# mega128board.net
KiCad netlist of a schematic drawn in EAGLE
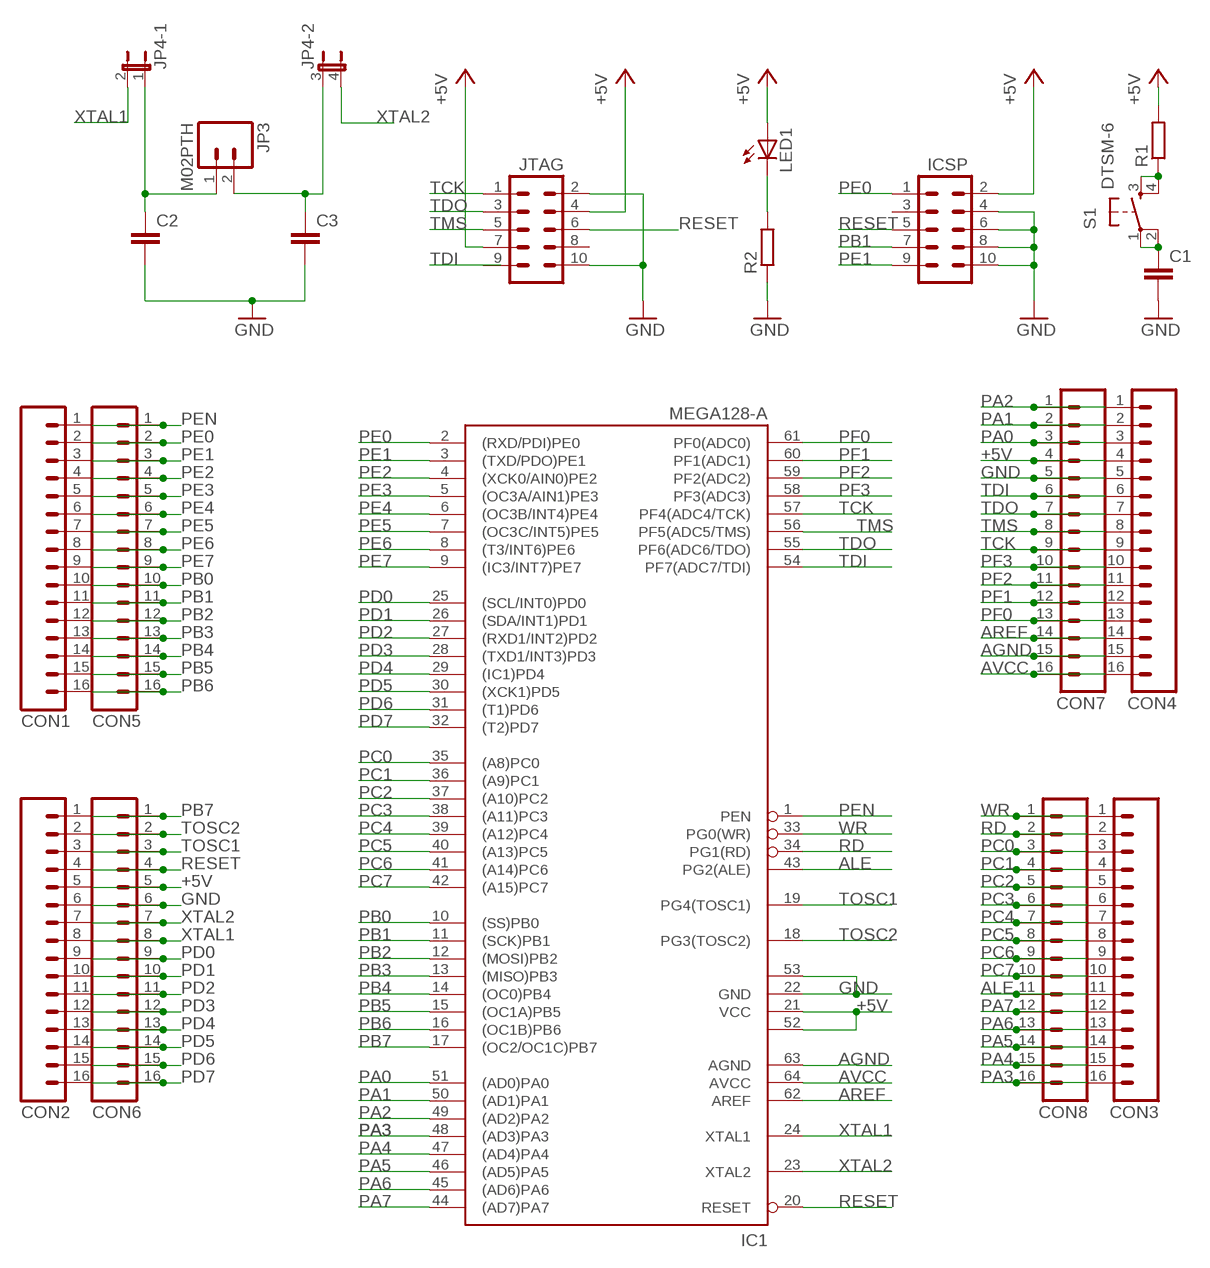
[diagram p0: schematic, sheet 1]

(export (version "E")
  (design (tool "Eeschema 10.0.6"))
  (components
    (comp (ref "C1")
      (value "C-EUC0805")
      (footprint "eagle-import:C0805")
      (libsource (lib "eagle-import") (part "C-EUC0805"))
    )
    (comp (ref "C2")
      (value "C-EUC0805")
      (footprint "eagle-import:C0805")
      (libsource (lib "eagle-import") (part "C-EUC0805"))
    )
    (comp (ref "C3")
      (value "C-EUC0805")
      (footprint "eagle-import:C0805")
      (libsource (lib "eagle-import") (part "C-EUC0805"))
    )
    (comp (ref "CON1")
      (value "M161X16_NO_SILK")
      (footprint "eagle-import:1X16_NO_SILK")
      (libsource (lib "eagle-import") (part "M161X16_NO_SILK"))
    )
    (comp (ref "CON2")
      (value "M161X16_NO_SILK")
      (footprint "eagle-import:1X16_NO_SILK")
      (libsource (lib "eagle-import") (part "M161X16_NO_SILK"))
    )
    (comp (ref "CON3")
      (value "M161X16_NO_SILK")
      (footprint "eagle-import:1X16_NO_SILK")
      (libsource (lib "eagle-import") (part "M161X16_NO_SILK"))
    )
    (comp (ref "CON4")
      (value "M161X16_NO_SILK")
      (footprint "eagle-import:1X16_NO_SILK")
      (libsource (lib "eagle-import") (part "M161X16_NO_SILK"))
    )
    (comp (ref "CON5")
      (value "M161X16_NO_SILK")
      (footprint "eagle-import:1X16_NO_SILK")
      (libsource (lib "eagle-import") (part "M161X16_NO_SILK"))
    )
    (comp (ref "CON6")
      (value "M161X16_NO_SILK")
      (footprint "eagle-import:1X16_NO_SILK")
      (libsource (lib "eagle-import") (part "M161X16_NO_SILK"))
    )
    (comp (ref "CON7")
      (value "M161X16_NO_SILK")
      (footprint "eagle-import:1X16_NO_SILK")
      (libsource (lib "eagle-import") (part "M161X16_NO_SILK"))
    )
    (comp (ref "CON8")
      (value "M161X16_NO_SILK")
      (footprint "eagle-import:1X16_NO_SILK")
      (libsource (lib "eagle-import") (part "M161X16_NO_SILK"))
    )
    (comp (ref "IC1")
      (value "MEGA128-A")
      (footprint "eagle-import:TQFP64")
      (libsource (lib "eagle-import") (part "MEGA128-A"))
    )
    (comp (ref "ICSP")
      (value "M05X2SHD")
      (footprint "eagle-import:2X5-SHROUDED")
      (libsource (lib "eagle-import") (part "M05X2SHD"))
    )
    (comp (ref "JP3")
      (value "M02PTH")
      (footprint "eagle-import:1X02")
      (libsource (lib "eagle-import") (part "M02PTH"))
    )
    (comp (ref "JP4")
      (value "JP2QE")
      (footprint "eagle-import:JP2Q")
      (libsource (lib "eagle-import") (part "JP2QE"))
    )
    (comp (ref "JTAG")
      (value "M05X2SHD")
      (footprint "eagle-import:2X5-SHROUDED")
      (libsource (lib "eagle-import") (part "M05X2SHD"))
    )
    (comp (ref "LED1")
      (value "LED1206")
      (footprint "eagle-import:LED-1206")
      (libsource (lib "eagle-import") (part "LED1206"))
    )
    (comp (ref "R1")
      (value "R-EU_M0805")
      (footprint "eagle-import:M0805")
      (libsource (lib "eagle-import") (part "R-EU_M0805"))
    )
    (comp (ref "R2")
      (value "R-EU_M0805")
      (footprint "eagle-import:M0805")
      (libsource (lib "eagle-import") (part "R-EU_M0805"))
    )
    (comp (ref "S1")
      (value "DTSM-6")
      (footprint "eagle-import:DTSM-6")
      (libsource (lib "eagle-import") (part "DTSM-6"))
    )
  )
  (nets
    (net (code "1") (name "+5V") (class "Default")
      (node (ref "CON2") (pin "5") (pinfunction "5_5") (pintype "passive"))
      (node (ref "CON4") (pin "4") (pinfunction "4_4") (pintype "passive"))
      (node (ref "CON6") (pin "5") (pinfunction "5_5") (pintype "passive"))
      (node (ref "CON7") (pin "4") (pinfunction "4_4") (pintype "passive"))
      (node (ref "IC1") (pin "21") (pinfunction "VCC_21") (pintype "power_in"))
      (node (ref "IC1") (pin "52") (pinfunction "VCC1_52") (pintype "power_in"))
      (node (ref "ICSP") (pin "2") (pinfunction "2_2") (pintype "passive"))
      (node (ref "JTAG") (pin "4") (pinfunction "4_4") (pintype "passive"))
      (node (ref "JTAG") (pin "7") (pinfunction "7_7") (pintype "passive"))
      (node (ref "LED1") (pin "A") (pinfunction "A_A") (pintype "passive"))
      (node (ref "R1") (pin "2") (pinfunction "2_2") (pintype "passive"))
    )
    (net (code "2") (name "/AGND") (class "Default")
      (node (ref "CON4") (pin "15") (pinfunction "15_15") (pintype "passive"))
      (node (ref "CON7") (pin "15") (pinfunction "15_15") (pintype "passive"))
      (node (ref "IC1") (pin "63") (pinfunction "AGND_63") (pintype "bidirectional"))
    )
    (net (code "3") (name "/ALE") (class "Default")
      (node (ref "CON3") (pin "11") (pinfunction "11_11") (pintype "passive"))
      (node (ref "CON8") (pin "11") (pinfunction "11_11") (pintype "passive"))
      (node (ref "IC1") (pin "43") (pinfunction "PG2(ALE)_43") (pintype "bidirectional"))
    )
    (net (code "4") (name "/AREF") (class "Default")
      (node (ref "CON4") (pin "14") (pinfunction "14_14") (pintype "passive"))
      (node (ref "CON7") (pin "14") (pinfunction "14_14") (pintype "passive"))
      (node (ref "IC1") (pin "62") (pinfunction "AREF_62") (pintype "bidirectional"))
    )
    (net (code "5") (name "/AVCC") (class "Default")
      (node (ref "CON4") (pin "16") (pinfunction "16_16") (pintype "passive"))
      (node (ref "CON7") (pin "16") (pinfunction "16_16") (pintype "passive"))
      (node (ref "IC1") (pin "64") (pinfunction "AVCC_64") (pintype "bidirectional"))
    )
    (net (code "6") (name "/PA0") (class "Default")
      (node (ref "CON4") (pin "3") (pinfunction "3_3") (pintype "passive"))
      (node (ref "CON7") (pin "3") (pinfunction "3_3") (pintype "passive"))
      (node (ref "IC1") (pin "51") (pinfunction "(AD0)PA0_51") (pintype "bidirectional"))
    )
    (net (code "7") (name "/PA1") (class "Default")
      (node (ref "CON4") (pin "2") (pinfunction "2_2") (pintype "passive"))
      (node (ref "CON7") (pin "2") (pinfunction "2_2") (pintype "passive"))
      (node (ref "IC1") (pin "50") (pinfunction "(AD1)PA1_50") (pintype "bidirectional"))
    )
    (net (code "8") (name "/PA2") (class "Default")
      (node (ref "CON4") (pin "1") (pinfunction "1_1") (pintype "passive"))
      (node (ref "CON7") (pin "1") (pinfunction "1_1") (pintype "passive"))
      (node (ref "IC1") (pin "49") (pinfunction "(AD2)PA2_49") (pintype "bidirectional"))
    )
    (net (code "9") (name "/PA3") (class "Default")
      (node (ref "CON3") (pin "16") (pinfunction "16_16") (pintype "passive"))
      (node (ref "CON8") (pin "16") (pinfunction "16_16") (pintype "passive"))
      (node (ref "IC1") (pin "48") (pinfunction "(AD3)PA3_48") (pintype "bidirectional"))
    )
    (net (code "10") (name "/PA4") (class "Default")
      (node (ref "CON3") (pin "15") (pinfunction "15_15") (pintype "passive"))
      (node (ref "CON8") (pin "15") (pinfunction "15_15") (pintype "passive"))
      (node (ref "IC1") (pin "47") (pinfunction "(AD4)PA4_47") (pintype "bidirectional"))
    )
    (net (code "11") (name "/PA5") (class "Default")
      (node (ref "CON3") (pin "14") (pinfunction "14_14") (pintype "passive"))
      (node (ref "CON8") (pin "14") (pinfunction "14_14") (pintype "passive"))
      (node (ref "IC1") (pin "46") (pinfunction "(AD5)PA5_46") (pintype "bidirectional"))
    )
    (net (code "12") (name "/PA6") (class "Default")
      (node (ref "CON3") (pin "13") (pinfunction "13_13") (pintype "passive"))
      (node (ref "CON8") (pin "13") (pinfunction "13_13") (pintype "passive"))
      (node (ref "IC1") (pin "45") (pinfunction "(AD6)PA6_45") (pintype "bidirectional"))
    )
    (net (code "13") (name "/PA7") (class "Default")
      (node (ref "CON3") (pin "12") (pinfunction "12_12") (pintype "passive"))
      (node (ref "CON8") (pin "12") (pinfunction "12_12") (pintype "passive"))
      (node (ref "IC1") (pin "44") (pinfunction "(AD7)PA7_44") (pintype "bidirectional"))
    )
    (net (code "14") (name "/PB0") (class "Default")
      (node (ref "CON1") (pin "10") (pinfunction "10_10") (pintype "passive"))
      (node (ref "CON5") (pin "10") (pinfunction "10_10") (pintype "passive"))
      (node (ref "IC1") (pin "10") (pinfunction "(SS)PB0_10") (pintype "bidirectional"))
    )
    (net (code "15") (name "/PB1") (class "Default")
      (node (ref "CON1") (pin "11") (pinfunction "11_11") (pintype "passive"))
      (node (ref "CON5") (pin "11") (pinfunction "11_11") (pintype "passive"))
      (node (ref "IC1") (pin "11") (pinfunction "(SCK)PB1_11") (pintype "bidirectional"))
      (node (ref "ICSP") (pin "7") (pinfunction "7_7") (pintype "passive"))
    )
    (net (code "16") (name "/PB2") (class "Default")
      (node (ref "CON1") (pin "12") (pinfunction "12_12") (pintype "passive"))
      (node (ref "CON5") (pin "12") (pinfunction "12_12") (pintype "passive"))
      (node (ref "IC1") (pin "12") (pinfunction "(MOSI)PB2_12") (pintype "bidirectional"))
    )
    (net (code "17") (name "/PB3") (class "Default")
      (node (ref "CON1") (pin "13") (pinfunction "13_13") (pintype "passive"))
      (node (ref "CON5") (pin "13") (pinfunction "13_13") (pintype "passive"))
      (node (ref "IC1") (pin "13") (pinfunction "(MISO)PB3_13") (pintype "bidirectional"))
    )
    (net (code "18") (name "/PB4") (class "Default")
      (node (ref "CON1") (pin "14") (pinfunction "14_14") (pintype "passive"))
      (node (ref "CON5") (pin "14") (pinfunction "14_14") (pintype "passive"))
      (node (ref "IC1") (pin "14") (pinfunction "(OC0)PB4_14") (pintype "bidirectional"))
    )
    (net (code "19") (name "/PB5") (class "Default")
      (node (ref "CON1") (pin "15") (pinfunction "15_15") (pintype "passive"))
      (node (ref "CON5") (pin "15") (pinfunction "15_15") (pintype "passive"))
      (node (ref "IC1") (pin "15") (pinfunction "(OC1A)PB5_15") (pintype "bidirectional"))
    )
    (net (code "20") (name "/PB6") (class "Default")
      (node (ref "CON1") (pin "16") (pinfunction "16_16") (pintype "passive"))
      (node (ref "CON5") (pin "16") (pinfunction "16_16") (pintype "passive"))
      (node (ref "IC1") (pin "16") (pinfunction "(OC1B)PB6_16") (pintype "bidirectional"))
    )
    (net (code "21") (name "/PB7") (class "Default")
      (node (ref "CON2") (pin "1") (pinfunction "1_1") (pintype "passive"))
      (node (ref "CON6") (pin "1") (pinfunction "1_1") (pintype "passive"))
      (node (ref "IC1") (pin "17") (pinfunction "(OC2/OC1C)PB7_17") (pintype "bidirectional"))
    )
    (net (code "22") (name "/PC0") (class "Default")
      (node (ref "CON3") (pin "3") (pinfunction "3_3") (pintype "passive"))
      (node (ref "CON8") (pin "3") (pinfunction "3_3") (pintype "passive"))
      (node (ref "IC1") (pin "35") (pinfunction "(A8)PC0_35") (pintype "output"))
    )
    (net (code "23") (name "/PC1") (class "Default")
      (node (ref "CON3") (pin "4") (pinfunction "4_4") (pintype "passive"))
      (node (ref "CON8") (pin "4") (pinfunction "4_4") (pintype "passive"))
      (node (ref "IC1") (pin "36") (pinfunction "(A9)PC1_36") (pintype "output"))
    )
    (net (code "24") (name "/PC2") (class "Default")
      (node (ref "CON3") (pin "5") (pinfunction "5_5") (pintype "passive"))
      (node (ref "CON8") (pin "5") (pinfunction "5_5") (pintype "passive"))
      (node (ref "IC1") (pin "37") (pinfunction "(A10)PC2_37") (pintype "output"))
    )
    (net (code "25") (name "/PC3") (class "Default")
      (node (ref "CON3") (pin "6") (pinfunction "6_6") (pintype "passive"))
      (node (ref "CON8") (pin "6") (pinfunction "6_6") (pintype "passive"))
      (node (ref "IC1") (pin "38") (pinfunction "(A11)PC3_38") (pintype "output"))
    )
    (net (code "26") (name "/PC4") (class "Default")
      (node (ref "CON3") (pin "7") (pinfunction "7_7") (pintype "passive"))
      (node (ref "CON8") (pin "7") (pinfunction "7_7") (pintype "passive"))
      (node (ref "IC1") (pin "39") (pinfunction "(A12)PC4_39") (pintype "output"))
    )
    (net (code "27") (name "/PC5") (class "Default")
      (node (ref "CON3") (pin "8") (pinfunction "8_8") (pintype "passive"))
      (node (ref "CON8") (pin "8") (pinfunction "8_8") (pintype "passive"))
      (node (ref "IC1") (pin "40") (pinfunction "(A13)PC5_40") (pintype "output"))
    )
    (net (code "28") (name "/PC6") (class "Default")
      (node (ref "CON3") (pin "9") (pinfunction "9_9") (pintype "passive"))
      (node (ref "CON8") (pin "9") (pinfunction "9_9") (pintype "passive"))
      (node (ref "IC1") (pin "41") (pinfunction "(A14)PC6_41") (pintype "output"))
    )
    (net (code "29") (name "/PC7") (class "Default")
      (node (ref "CON3") (pin "10") (pinfunction "10_10") (pintype "passive"))
      (node (ref "CON8") (pin "10") (pinfunction "10_10") (pintype "passive"))
      (node (ref "IC1") (pin "42") (pinfunction "(A15)PC7_42") (pintype "output"))
    )
    (net (code "30") (name "/PD0") (class "Default")
      (node (ref "CON2") (pin "9") (pinfunction "9_9") (pintype "passive"))
      (node (ref "CON6") (pin "9") (pinfunction "9_9") (pintype "passive"))
      (node (ref "IC1") (pin "25") (pinfunction "(SCL/INT0)PD0_25") (pintype "bidirectional"))
    )
    (net (code "31") (name "/PD1") (class "Default")
      (node (ref "CON2") (pin "10") (pinfunction "10_10") (pintype "passive"))
      (node (ref "CON6") (pin "10") (pinfunction "10_10") (pintype "passive"))
      (node (ref "IC1") (pin "26") (pinfunction "(SDA/INT1)PD1_26") (pintype "bidirectional"))
    )
    (net (code "32") (name "/PD2") (class "Default")
      (node (ref "CON2") (pin "11") (pinfunction "11_11") (pintype "passive"))
      (node (ref "CON6") (pin "11") (pinfunction "11_11") (pintype "passive"))
      (node (ref "IC1") (pin "27") (pinfunction "(RXD1/INT2)PD2_27") (pintype "bidirectional"))
    )
    (net (code "33") (name "/PD3") (class "Default")
      (node (ref "CON2") (pin "12") (pinfunction "12_12") (pintype "passive"))
      (node (ref "CON6") (pin "12") (pinfunction "12_12") (pintype "passive"))
      (node (ref "IC1") (pin "28") (pinfunction "(TXD1/INT3)PD3_28") (pintype "bidirectional"))
    )
    (net (code "34") (name "/PD4") (class "Default")
      (node (ref "CON2") (pin "13") (pinfunction "13_13") (pintype "passive"))
      (node (ref "CON6") (pin "13") (pinfunction "13_13") (pintype "passive"))
      (node (ref "IC1") (pin "29") (pinfunction "(IC1)PD4_29") (pintype "bidirectional"))
    )
    (net (code "35") (name "/PD5") (class "Default")
      (node (ref "CON2") (pin "14") (pinfunction "14_14") (pintype "passive"))
      (node (ref "CON6") (pin "14") (pinfunction "14_14") (pintype "passive"))
      (node (ref "IC1") (pin "30") (pinfunction "(XCK1)PD5_30") (pintype "bidirectional"))
    )
    (net (code "36") (name "/PD6") (class "Default")
      (node (ref "CON2") (pin "15") (pinfunction "15_15") (pintype "passive"))
      (node (ref "CON6") (pin "15") (pinfunction "15_15") (pintype "passive"))
      (node (ref "IC1") (pin "31") (pinfunction "(T1)PD6_31") (pintype "bidirectional"))
    )
    (net (code "37") (name "/PD7") (class "Default")
      (node (ref "CON2") (pin "16") (pinfunction "16_16") (pintype "passive"))
      (node (ref "CON6") (pin "16") (pinfunction "16_16") (pintype "passive"))
      (node (ref "IC1") (pin "32") (pinfunction "(T2)PD7_32") (pintype "bidirectional"))
    )
    (net (code "38") (name "/PE0") (class "Default")
      (node (ref "CON1") (pin "2") (pinfunction "2_2") (pintype "passive"))
      (node (ref "CON5") (pin "2") (pinfunction "2_2") (pintype "passive"))
      (node (ref "IC1") (pin "2") (pinfunction "(RXD/PDI)PE0_2") (pintype "bidirectional"))
      (node (ref "ICSP") (pin "1") (pinfunction "1_1") (pintype "passive"))
    )
    (net (code "39") (name "/PE1") (class "Default")
      (node (ref "CON1") (pin "3") (pinfunction "3_3") (pintype "passive"))
      (node (ref "CON5") (pin "3") (pinfunction "3_3") (pintype "passive"))
      (node (ref "IC1") (pin "3") (pinfunction "(TXD/PDO)PE1_3") (pintype "bidirectional"))
      (node (ref "ICSP") (pin "9") (pinfunction "9_9") (pintype "passive"))
    )
    (net (code "40") (name "/PE2") (class "Default")
      (node (ref "CON1") (pin "4") (pinfunction "4_4") (pintype "passive"))
      (node (ref "CON5") (pin "4") (pinfunction "4_4") (pintype "passive"))
      (node (ref "IC1") (pin "4") (pinfunction "(XCK0/AIN0)PE2_4") (pintype "bidirectional"))
    )
    (net (code "41") (name "/PE3") (class "Default")
      (node (ref "CON1") (pin "5") (pinfunction "5_5") (pintype "passive"))
      (node (ref "CON5") (pin "5") (pinfunction "5_5") (pintype "passive"))
      (node (ref "IC1") (pin "5") (pinfunction "(OC3A/AIN1)PE3_5") (pintype "bidirectional"))
    )
    (net (code "42") (name "/PE4") (class "Default")
      (node (ref "CON1") (pin "6") (pinfunction "6_6") (pintype "passive"))
      (node (ref "CON5") (pin "6") (pinfunction "6_6") (pintype "passive"))
      (node (ref "IC1") (pin "6") (pinfunction "(OC3B/INT4)PE4_6") (pintype "bidirectional"))
    )
    (net (code "43") (name "/PE5") (class "Default")
      (node (ref "CON1") (pin "7") (pinfunction "7_7") (pintype "passive"))
      (node (ref "CON5") (pin "7") (pinfunction "7_7") (pintype "passive"))
      (node (ref "IC1") (pin "7") (pinfunction "(OC3C/INT5)PE5_7") (pintype "bidirectional"))
    )
    (net (code "44") (name "/PE6") (class "Default")
      (node (ref "CON1") (pin "8") (pinfunction "8_8") (pintype "passive"))
      (node (ref "CON5") (pin "8") (pinfunction "8_8") (pintype "passive"))
      (node (ref "IC1") (pin "8") (pinfunction "(T3/INT6)PE6_8") (pintype "bidirectional"))
    )
    (net (code "45") (name "/PE7") (class "Default")
      (node (ref "CON1") (pin "9") (pinfunction "9_9") (pintype "passive"))
      (node (ref "CON5") (pin "9") (pinfunction "9_9") (pintype "passive"))
      (node (ref "IC1") (pin "9") (pinfunction "(IC3/INT7)PE7_9") (pintype "bidirectional"))
    )
    (net (code "46") (name "/PEN") (class "Default")
      (node (ref "CON1") (pin "1") (pinfunction "1_1") (pintype "passive"))
      (node (ref "CON5") (pin "1") (pinfunction "1_1") (pintype "passive"))
      (node (ref "IC1") (pin "1") (pinfunction "PEN_1") (pintype "input"))
    )
    (net (code "47") (name "/PF0") (class "Default")
      (node (ref "CON4") (pin "13") (pinfunction "13_13") (pintype "passive"))
      (node (ref "CON7") (pin "13") (pinfunction "13_13") (pintype "passive"))
      (node (ref "IC1") (pin "61") (pinfunction "PF0(ADC0)_61") (pintype "input"))
    )
    (net (code "48") (name "/PF1") (class "Default")
      (node (ref "CON4") (pin "12") (pinfunction "12_12") (pintype "passive"))
      (node (ref "CON7") (pin "12") (pinfunction "12_12") (pintype "passive"))
      (node (ref "IC1") (pin "60") (pinfunction "PF1(ADC1)_60") (pintype "input"))
    )
    (net (code "49") (name "/PF2") (class "Default")
      (node (ref "CON4") (pin "11") (pinfunction "11_11") (pintype "passive"))
      (node (ref "CON7") (pin "11") (pinfunction "11_11") (pintype "passive"))
      (node (ref "IC1") (pin "59") (pinfunction "PF2(ADC2)_59") (pintype "input"))
    )
    (net (code "50") (name "/PF3") (class "Default")
      (node (ref "CON4") (pin "10") (pinfunction "10_10") (pintype "passive"))
      (node (ref "CON7") (pin "10") (pinfunction "10_10") (pintype "passive"))
      (node (ref "IC1") (pin "58") (pinfunction "PF3(ADC3)_58") (pintype "input"))
    )
    (net (code "51") (name "/RD") (class "Default")
      (node (ref "CON3") (pin "2") (pinfunction "2_2") (pintype "passive"))
      (node (ref "CON8") (pin "2") (pinfunction "2_2") (pintype "passive"))
      (node (ref "IC1") (pin "34") (pinfunction "PG1(RD)_34") (pintype "bidirectional"))
    )
    (net (code "52") (name "/RESET") (class "Default")
      (node (ref "CON2") (pin "4") (pinfunction "4_4") (pintype "passive"))
      (node (ref "CON6") (pin "4") (pinfunction "4_4") (pintype "passive"))
      (node (ref "IC1") (pin "20") (pinfunction "RESET_20") (pintype "input"))
      (node (ref "ICSP") (pin "5") (pinfunction "5_5") (pintype "passive"))
      (node (ref "JTAG") (pin "6") (pinfunction "6_6") (pintype "passive"))
    )
    (net (code "53") (name "/TCK") (class "Default")
      (node (ref "CON4") (pin "9") (pinfunction "9_9") (pintype "passive"))
      (node (ref "CON7") (pin "9") (pinfunction "9_9") (pintype "passive"))
      (node (ref "IC1") (pin "57") (pinfunction "PF4(ADC4/TCK)_57") (pintype "input"))
      (node (ref "JTAG") (pin "1") (pinfunction "1_1") (pintype "passive"))
    )
    (net (code "54") (name "/TDI") (class "Default")
      (node (ref "CON4") (pin "6") (pinfunction "6_6") (pintype "passive"))
      (node (ref "CON7") (pin "6") (pinfunction "6_6") (pintype "passive"))
      (node (ref "IC1") (pin "54") (pinfunction "PF7(ADC7/TDI)_54") (pintype "input"))
    )
    (net (code "55") (name "/TDO") (class "Default")
      (node (ref "CON4") (pin "7") (pinfunction "7_7") (pintype "passive"))
      (node (ref "CON7") (pin "7") (pinfunction "7_7") (pintype "passive"))
      (node (ref "IC1") (pin "55") (pinfunction "PF6(ADC6/TDO)_55") (pintype "input"))
      (node (ref "JTAG") (pin "3") (pinfunction "3_3") (pintype "passive"))
    )
    (net (code "56") (name "/TMS") (class "Default")
      (node (ref "CON4") (pin "8") (pinfunction "8_8") (pintype "passive"))
      (node (ref "CON7") (pin "8") (pinfunction "8_8") (pintype "passive"))
      (node (ref "IC1") (pin "56") (pinfunction "PF5(ADC5/TMS)_56") (pintype "input"))
      (node (ref "JTAG") (pin "5") (pinfunction "5_5") (pintype "passive"))
    )
    (net (code "57") (name "/TOSC1") (class "Default")
      (node (ref "CON2") (pin "3") (pinfunction "3_3") (pintype "passive"))
      (node (ref "CON6") (pin "3") (pinfunction "3_3") (pintype "passive"))
      (node (ref "IC1") (pin "19") (pinfunction "PG4(TOSC1)_19") (pintype "bidirectional"))
    )
    (net (code "58") (name "/TOSC2") (class "Default")
      (node (ref "CON2") (pin "2") (pinfunction "2_2") (pintype "passive"))
      (node (ref "CON6") (pin "2") (pinfunction "2_2") (pintype "passive"))
      (node (ref "IC1") (pin "18") (pinfunction "PG3(TOSC2)_18") (pintype "bidirectional"))
    )
    (net (code "59") (name "/WR") (class "Default")
      (node (ref "CON3") (pin "1") (pinfunction "1_1") (pintype "passive"))
      (node (ref "CON8") (pin "1") (pinfunction "1_1") (pintype "passive"))
      (node (ref "IC1") (pin "33") (pinfunction "PG0(WR)_33") (pintype "bidirectional"))
    )
    (net (code "60") (name "/XTAL1") (class "Default")
      (node (ref "CON2") (pin "8") (pinfunction "8_8") (pintype "passive"))
      (node (ref "CON6") (pin "8") (pinfunction "8_8") (pintype "passive"))
      (node (ref "IC1") (pin "24") (pinfunction "XTAL1_24") (pintype "bidirectional"))
      (node (ref "JP4") (pin "2") (pinfunction "2_2") (pintype "passive"))
    )
    (net (code "61") (name "/XTAL2") (class "Default")
      (node (ref "CON2") (pin "7") (pinfunction "7_7") (pintype "passive"))
      (node (ref "CON6") (pin "7") (pinfunction "7_7") (pintype "passive"))
      (node (ref "IC1") (pin "23") (pinfunction "XTAL2_23") (pintype "bidirectional"))
      (node (ref "JP4") (pin "4") (pinfunction "2_4") (pintype "passive"))
    )
    (net (code "62") (name "GND") (class "Default")
      (node (ref "C1") (pin "2") (pinfunction "2_2") (pintype "passive"))
      (node (ref "C2") (pin "2") (pinfunction "2_2") (pintype "passive"))
      (node (ref "C3") (pin "2") (pinfunction "2_2") (pintype "passive"))
      (node (ref "CON2") (pin "6") (pinfunction "6_6") (pintype "passive"))
      (node (ref "CON4") (pin "5") (pinfunction "5_5") (pintype "passive"))
      (node (ref "CON6") (pin "6") (pinfunction "6_6") (pintype "passive"))
      (node (ref "CON7") (pin "5") (pinfunction "5_5") (pintype "passive"))
      (node (ref "IC1") (pin "22") (pinfunction "GND_22") (pintype "power_in"))
      (node (ref "IC1") (pin "53") (pinfunction "GND1_53") (pintype "power_in"))
      (node (ref "ICSP") (pin "10") (pinfunction "10_10") (pintype "passive"))
      (node (ref "ICSP") (pin "4") (pinfunction "4_4") (pintype "passive"))
      (node (ref "ICSP") (pin "6") (pinfunction "6_6") (pintype "passive"))
      (node (ref "ICSP") (pin "8") (pinfunction "8_8") (pintype "passive"))
      (node (ref "JTAG") (pin "10") (pinfunction "10_10") (pintype "passive"))
      (node (ref "JTAG") (pin "2") (pinfunction "2_2") (pintype "passive"))
      (node (ref "R2") (pin "1") (pinfunction "1_1") (pintype "passive"))
    )
    (net (code "63") (name "Net-(C1-Pad1)") (class "Default")
      (node (ref "C1") (pin "1") (pinfunction "1_1") (pintype "passive"))
      (node (ref "S1") (pin "1") (pinfunction "1_1") (pintype "passive"))
      (node (ref "S1") (pin "2") (pinfunction "2_2") (pintype "passive"))
    )
    (net (code "64") (name "Net-(C2-Pad1)") (class "Default")
      (node (ref "C2") (pin "1") (pinfunction "1_1") (pintype "passive"))
      (node (ref "JP3") (pin "1") (pinfunction "1_1") (pintype "passive"))
      (node (ref "JP4") (pin "1") (pinfunction "1_1") (pintype "passive"))
    )
    (net (code "65") (name "Net-(JP4B-1)") (class "Default")
      (node (ref "C3") (pin "1") (pinfunction "1_1") (pintype "passive"))
      (node (ref "JP3") (pin "2") (pinfunction "2_2") (pintype "passive"))
      (node (ref "JP4") (pin "3") (pinfunction "1_3") (pintype "passive"))
    )
    (net (code "66") (name "Net-(LED1-PadC)") (class "Default")
      (node (ref "LED1") (pin "C") (pinfunction "C_C") (pintype "passive"))
      (node (ref "R2") (pin "2") (pinfunction "2_2") (pintype "passive"))
    )
    (net (code "67") (name "Net-(R1-Pad1)") (class "Default")
      (node (ref "R1") (pin "1") (pinfunction "1_1") (pintype "passive"))
      (node (ref "S1") (pin "3") (pinfunction "3_3") (pintype "passive"))
      (node (ref "S1") (pin "4") (pinfunction "4_4") (pintype "passive"))
    )
    (net (code "68") (name "unconnected-(ICSP-Pad3)") (class "Default")
      (node (ref "ICSP") (pin "3") (pinfunction "3_3") (pintype "passive"))
    )
    (net (code "69") (name "unconnected-(JTAG-Pad8)") (class "Default")
      (node (ref "JTAG") (pin "8") (pinfunction "8_8") (pintype "passive"))
    )
    (net (code "70") (name "unconnected-(JTAG-Pad9)") (class "Default")
      (node (ref "JTAG") (pin "9") (pinfunction "9_9") (pintype "passive"))
    )
  )
)
